# RAM_MAR_Circuit_Electronic_Scheme_2021-1.net
KiCad netlist of a schematic drawn in Altium Designer
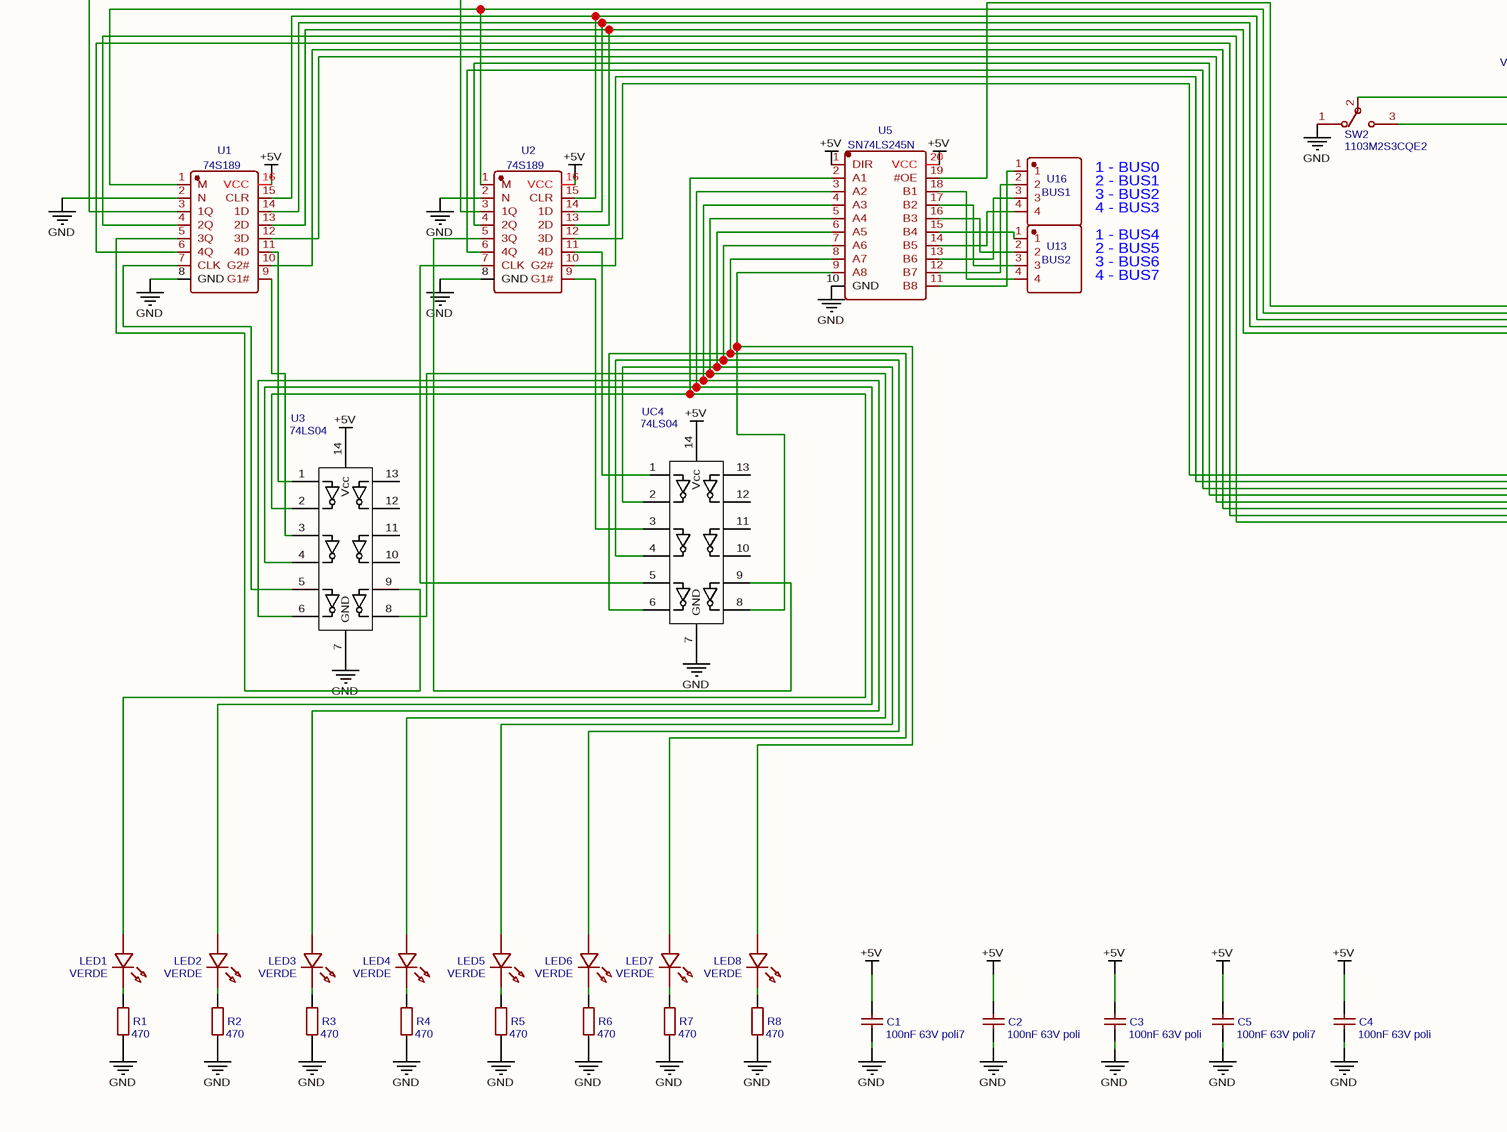
[diagram p0: RAM & MAR Circuit Electronic Scheme_2021-12-04.schdoc, left]
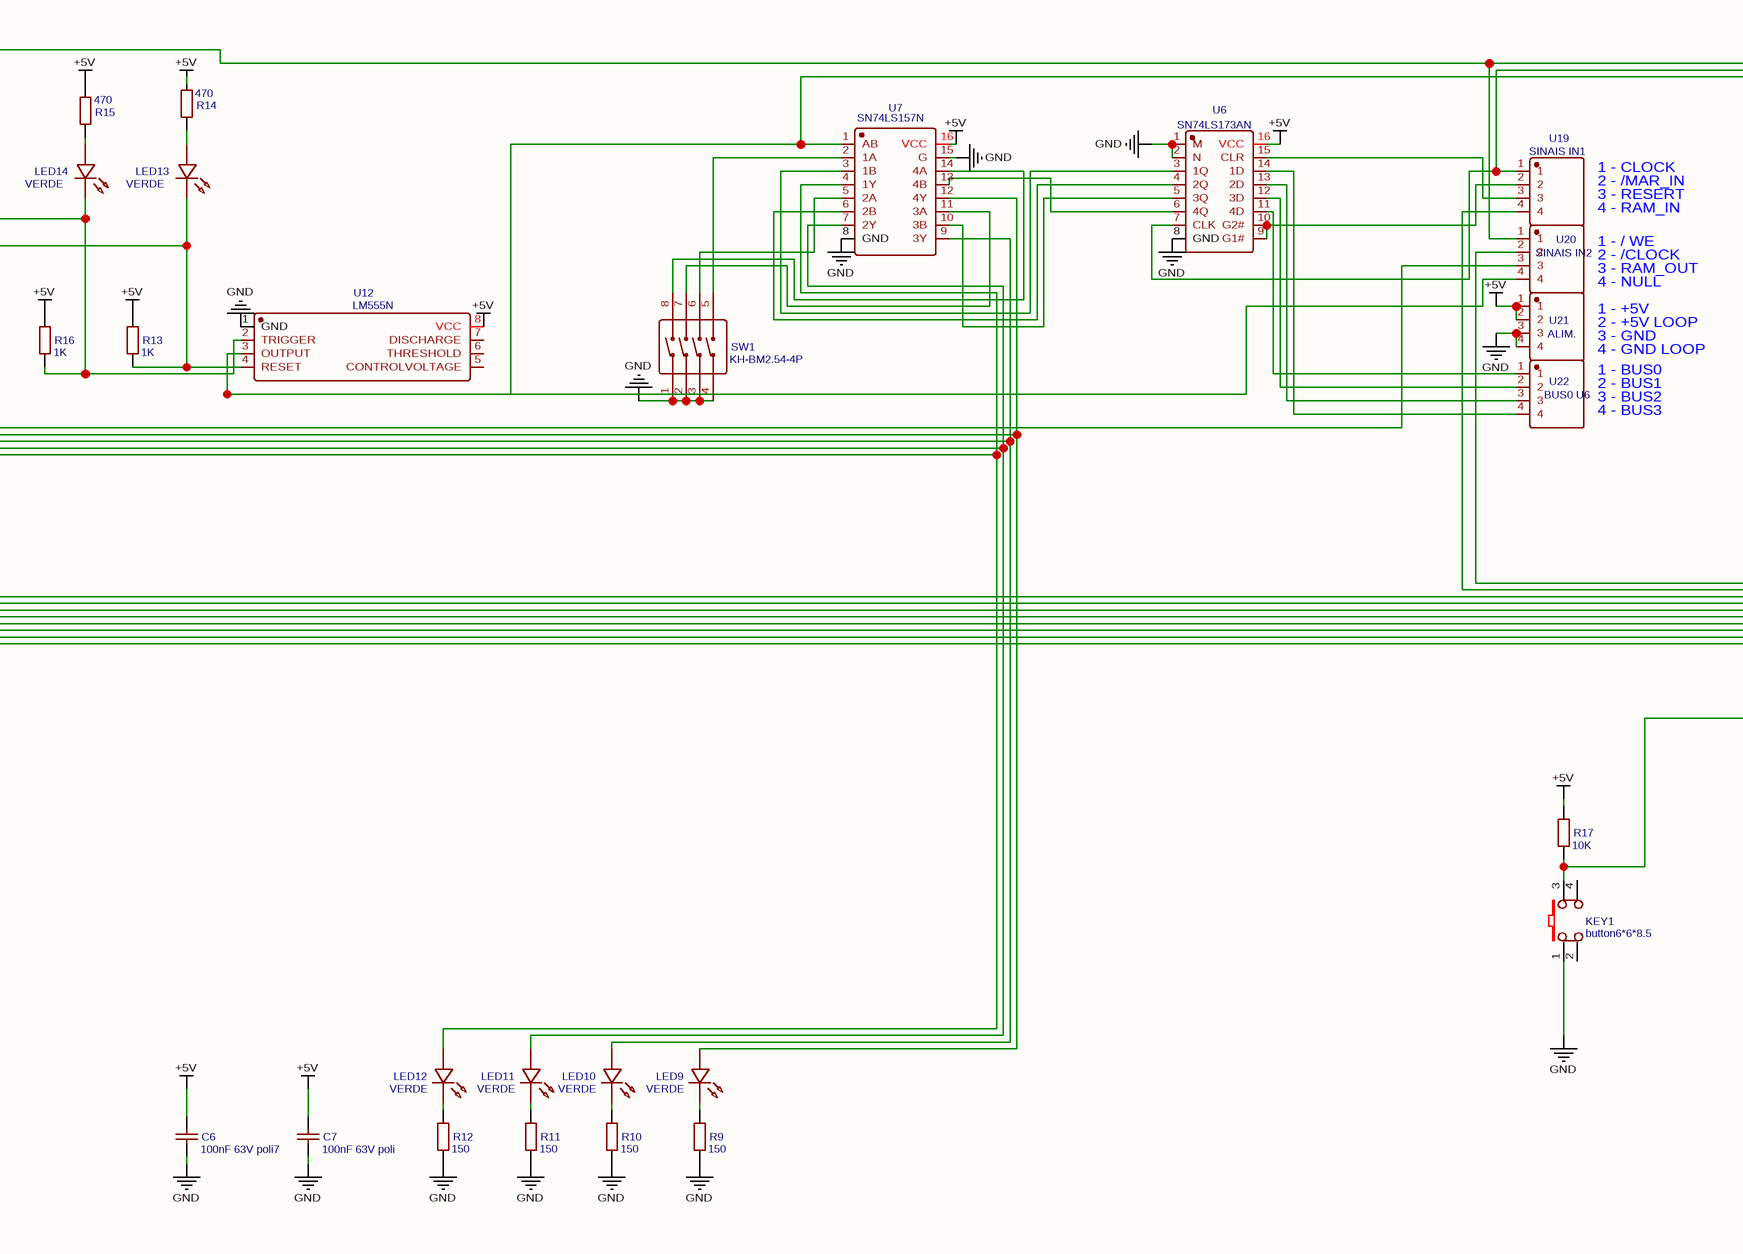
[diagram p1: RAM & MAR Circuit Electronic Scheme_2021-12-04.schdoc, middle]
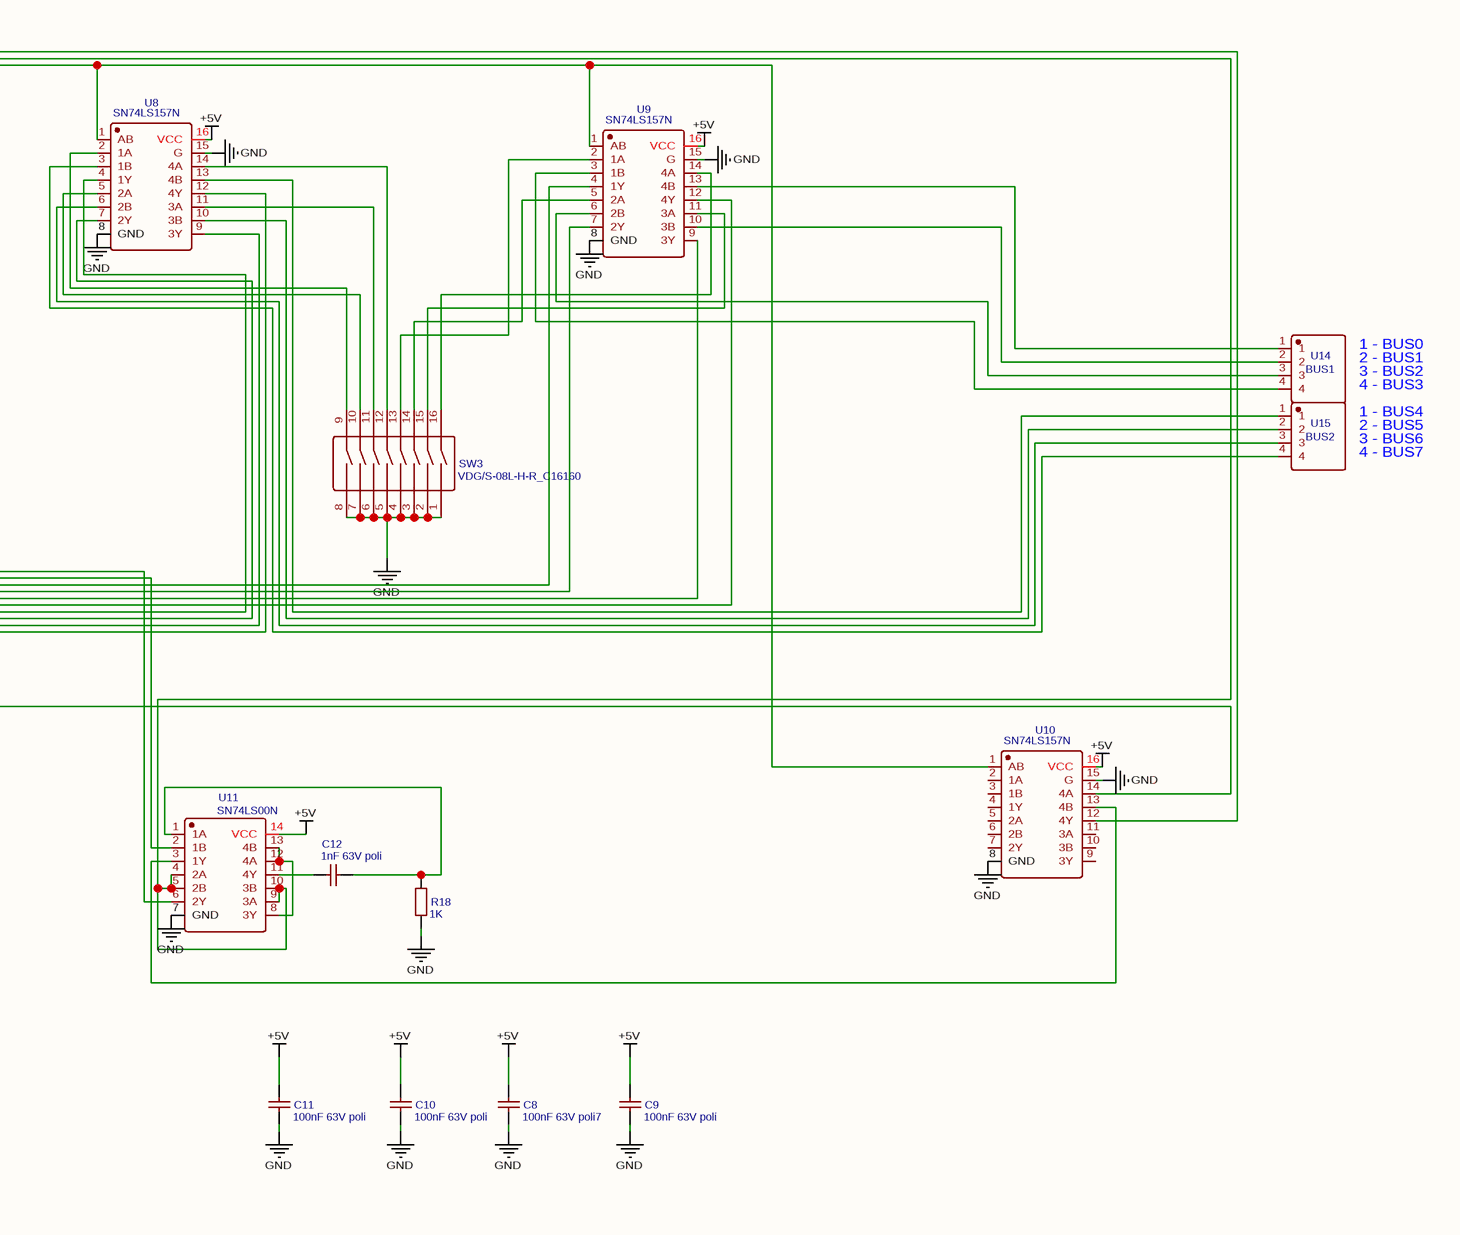
[diagram p2: RAM & MAR Circuit Electronic Scheme_2021-12-04.schdoc, right]

(export (version "E")
  (design (tool "Eeschema 10.0.6"))
  (components
    (comp (ref "C1")
      (value "100nF 63V poli7")
      (fields
        (field (name "BOM_SUPPLIER PART") "C444741")
        (field (name "BOM_MANUFACTURER PART") "SR305C105KAR")
      )
      (libsource (lib "altium-import") (part "root_3_100nF 63V poli7_"))
    )
    (comp (ref "C2")
      (value "100nF 63V poli")
      (fields
        (field (name "BOM_SUPPLIER PART") "C444741")
        (field (name "BOM_MANUFACTURER PART") "SR305C105KAR")
      )
      (libsource (lib "altium-import") (part "root_3_100nF 63V poli_"))
    )
    (comp (ref "C3")
      (value "100nF 63V poli")
      (fields
        (field (name "BOM_SUPPLIER PART") "C444741")
        (field (name "BOM_MANUFACTURER PART") "SR305C105KAR")
      )
      (libsource (lib "altium-import") (part "root_3_100nF 63V poli_"))
    )
    (comp (ref "C4")
      (value "100nF 63V poli")
      (fields
        (field (name "BOM_SUPPLIER PART") "C444741")
        (field (name "BOM_MANUFACTURER PART") "SR305C105KAR")
      )
      (libsource (lib "altium-import") (part "root_3_100nF 63V poli_"))
    )
    (comp (ref "C5")
      (value "100nF 63V poli7")
      (fields
        (field (name "BOM_SUPPLIER PART") "C444741")
        (field (name "BOM_MANUFACTURER PART") "SR305C105KAR")
      )
      (libsource (lib "altium-import") (part "root_3_100nF 63V poli7_"))
    )
    (comp (ref "C6")
      (value "100nF 63V poli7")
      (fields
        (field (name "BOM_SUPPLIER PART") "C444741")
        (field (name "BOM_MANUFACTURER PART") "SR305C105KAR")
      )
      (libsource (lib "altium-import") (part "root_3_100nF 63V poli7_"))
    )
    (comp (ref "C7")
      (value "100nF 63V poli")
      (fields
        (field (name "BOM_SUPPLIER PART") "C444741")
        (field (name "BOM_MANUFACTURER PART") "SR305C105KAR")
      )
      (libsource (lib "altium-import") (part "root_3_100nF 63V poli_"))
    )
    (comp (ref "C8")
      (value "100nF 63V poli7")
      (fields
        (field (name "BOM_SUPPLIER PART") "C444741")
        (field (name "BOM_MANUFACTURER PART") "SR305C105KAR")
      )
      (libsource (lib "altium-import") (part "root_3_100nF 63V poli7_"))
    )
    (comp (ref "C9")
      (value "100nF 63V poli")
      (fields
        (field (name "BOM_SUPPLIER PART") "C444741")
        (field (name "BOM_MANUFACTURER PART") "SR305C105KAR")
      )
      (libsource (lib "altium-import") (part "root_3_100nF 63V poli_"))
    )
    (comp (ref "C10")
      (value "100nF 63V poli")
      (fields
        (field (name "BOM_SUPPLIER PART") "C444741")
        (field (name "BOM_MANUFACTURER PART") "SR305C105KAR")
      )
      (libsource (lib "altium-import") (part "root_3_100nF 63V poli_"))
    )
    (comp (ref "C11")
      (value "100nF 63V poli")
      (fields
        (field (name "BOM_SUPPLIER PART") "C444741")
        (field (name "BOM_MANUFACTURER PART") "SR305C105KAR")
      )
      (libsource (lib "altium-import") (part "root_3_100nF 63V poli_"))
    )
    (comp (ref "C12")
      (value "1nF 63V poli")
      (fields
        (field (name "BOM_SUPPLIER PART") "C444741")
        (field (name "BOM_MANUFACTURER PART") "SR305C105KAR")
      )
      (libsource (lib "altium-import") (part "root_0_1nF 63V poli_"))
    )
    (comp (ref "KEY1")
      (value "button6*6*8.5")
      (fields (field (name "BOM_SUPPLIER PART") "C59980"))
      (libsource (lib "altium-import") (part "root_1_button6*6*8.5_"))
    )
    (comp (ref "LED1")
      (value "VERDE")
      (fields (field (name "BOM_SUPPLIER PART") "C605465") (field (name "BOM_MANUFACTURER PART") "264-7GD"))
      (libsource (lib "altium-import") (part "root_1_VERDE_"))
    )
    (comp (ref "LED2")
      (value "VERDE")
      (fields (field (name "BOM_SUPPLIER PART") "C605465") (field (name "BOM_MANUFACTURER PART") "264-7GD"))
      (libsource (lib "altium-import") (part "root_1_VERDE_"))
    )
    (comp (ref "LED3")
      (value "VERDE")
      (fields (field (name "BOM_SUPPLIER PART") "C605465") (field (name "BOM_MANUFACTURER PART") "264-7GD"))
      (libsource (lib "altium-import") (part "root_1_VERDE_"))
    )
    (comp (ref "LED4")
      (value "VERDE")
      (fields (field (name "BOM_SUPPLIER PART") "C605465") (field (name "BOM_MANUFACTURER PART") "264-7GD"))
      (libsource (lib "altium-import") (part "root_1_VERDE_"))
    )
    (comp (ref "LED5")
      (value "VERDE")
      (fields (field (name "BOM_SUPPLIER PART") "C605465") (field (name "BOM_MANUFACTURER PART") "264-7GD"))
      (libsource (lib "altium-import") (part "root_1_VERDE_"))
    )
    (comp (ref "LED6")
      (value "VERDE")
      (fields (field (name "BOM_SUPPLIER PART") "C605465") (field (name "BOM_MANUFACTURER PART") "264-7GD"))
      (libsource (lib "altium-import") (part "root_1_VERDE_"))
    )
    (comp (ref "LED7")
      (value "VERDE")
      (fields (field (name "BOM_SUPPLIER PART") "C605465") (field (name "BOM_MANUFACTURER PART") "264-7GD"))
      (libsource (lib "altium-import") (part "root_1_VERDE_"))
    )
    (comp (ref "LED8")
      (value "VERDE")
      (fields (field (name "BOM_SUPPLIER PART") "C605465") (field (name "BOM_MANUFACTURER PART") "264-7GD"))
      (libsource (lib "altium-import") (part "root_1_VERDE_"))
    )
    (comp (ref "LED9")
      (value "VERDE")
      (fields (field (name "BOM_SUPPLIER PART") "C605465") (field (name "BOM_MANUFACTURER PART") "264-7GD"))
      (libsource (lib "altium-import") (part "root_1_VERDE_"))
    )
    (comp (ref "LED10")
      (value "VERDE")
      (fields (field (name "BOM_SUPPLIER PART") "C605465") (field (name "BOM_MANUFACTURER PART") "264-7GD"))
      (libsource (lib "altium-import") (part "root_1_VERDE_"))
    )
    (comp (ref "LED11")
      (value "VERDE")
      (fields (field (name "BOM_SUPPLIER PART") "C605465") (field (name "BOM_MANUFACTURER PART") "264-7GD"))
      (libsource (lib "altium-import") (part "root_1_VERDE_"))
    )
    (comp (ref "LED12")
      (value "VERDE")
      (fields (field (name "BOM_SUPPLIER PART") "C605465") (field (name "BOM_MANUFACTURER PART") "264-7GD"))
      (libsource (lib "altium-import") (part "root_1_VERDE_"))
    )
    (comp (ref "LED13")
      (value "VERDE")
      (fields (field (name "BOM_SUPPLIER PART") "C605465") (field (name "BOM_MANUFACTURER PART") "264-7GD"))
      (libsource (lib "altium-import") (part "root_3_VERDE_"))
    )
    (comp (ref "LED14")
      (value "VERDE")
      (fields (field (name "BOM_SUPPLIER PART") "C605465") (field (name "BOM_MANUFACTURER PART") "264-7GD"))
      (libsource (lib "altium-import") (part "root_3_VERDE_"))
    )
    (comp (ref "R1")
      (value "470")
      (fields
        (field (name "BOM_MANUFACTURER PART") "CFR02SJ0823A10")
        (field (name "BOM_SUPPLIER PART") "C69876")
      )
      (libsource (lib "") (part "root_3_470__1"))
    )
    (comp (ref "R2")
      (value "470")
      (fields
        (field (name "BOM_MANUFACTURER PART") "CFR02SJ0823A10")
        (field (name "BOM_SUPPLIER PART") "C69876")
      )
      (libsource (lib "") (part "root_3_470__1"))
    )
    (comp (ref "R3")
      (value "470")
      (fields
        (field (name "BOM_MANUFACTURER PART") "CFR02SJ0823A10")
        (field (name "BOM_SUPPLIER PART") "C69876")
      )
      (libsource (lib "") (part "root_3_470__1"))
    )
    (comp (ref "R4")
      (value "470")
      (fields
        (field (name "BOM_MANUFACTURER PART") "CFR02SJ0823A10")
        (field (name "BOM_SUPPLIER PART") "C69876")
      )
      (libsource (lib "") (part "root_3_470__1"))
    )
    (comp (ref "R5")
      (value "470")
      (fields
        (field (name "BOM_MANUFACTURER PART") "CFR02SJ0823A10")
        (field (name "BOM_SUPPLIER PART") "C69876")
      )
      (libsource (lib "") (part "root_3_470__1"))
    )
    (comp (ref "R6")
      (value "470")
      (fields
        (field (name "BOM_MANUFACTURER PART") "CFR02SJ0823A10")
        (field (name "BOM_SUPPLIER PART") "C69876")
      )
      (libsource (lib "") (part "root_3_470__1"))
    )
    (comp (ref "R7")
      (value "470")
      (fields
        (field (name "BOM_MANUFACTURER PART") "CFR02SJ0823A10")
        (field (name "BOM_SUPPLIER PART") "C69876")
      )
      (libsource (lib "") (part "root_3_470__1"))
    )
    (comp (ref "R8")
      (value "470")
      (fields
        (field (name "BOM_MANUFACTURER PART") "CFR02SJ0823A10")
        (field (name "BOM_SUPPLIER PART") "C69876")
      )
      (libsource (lib "") (part "root_3_470__1"))
    )
    (comp (ref "R9")
      (value "150")
      (fields
        (field (name "BOM_MANUFACTURER PART") "CFR02SJ0823A10")
        (field (name "BOM_SUPPLIER PART") "C69876")
      )
      (libsource (lib "altium-import") (part "root_3_150_"))
    )
    (comp (ref "R10")
      (value "150")
      (fields
        (field (name "BOM_MANUFACTURER PART") "CFR02SJ0823A10")
        (field (name "BOM_SUPPLIER PART") "C69876")
      )
      (libsource (lib "altium-import") (part "root_3_150_"))
    )
    (comp (ref "R11")
      (value "150")
      (fields
        (field (name "BOM_MANUFACTURER PART") "CFR02SJ0823A10")
        (field (name "BOM_SUPPLIER PART") "C69876")
      )
      (libsource (lib "altium-import") (part "root_3_150_"))
    )
    (comp (ref "R12")
      (value "150")
      (fields
        (field (name "BOM_MANUFACTURER PART") "CFR02SJ0823A10")
        (field (name "BOM_SUPPLIER PART") "C69876")
      )
      (libsource (lib "altium-import") (part "root_3_150_"))
    )
    (comp (ref "R13")
      (value "1K")
      (fields
        (field (name "BOM_MANUFACTURER PART") "CFR02SJ0823A10")
        (field (name "BOM_SUPPLIER PART") "C69876")
      )
      (libsource (lib "altium-import") (part "root_3_1K_"))
    )
    (comp (ref "R14")
      (value "470")
      (fields
        (field (name "BOM_MANUFACTURER PART") "CFR02SJ0823A10")
        (field (name "BOM_SUPPLIER PART") "C69876")
      )
      (libsource (lib "altium-import") (part "root_3_470_"))
    )
    (comp (ref "R15")
      (value "470")
      (fields
        (field (name "BOM_MANUFACTURER PART") "CFR02SJ0823A10")
        (field (name "BOM_SUPPLIER PART") "C69876")
      )
      (libsource (lib "altium-import") (part "root_3_470_"))
    )
    (comp (ref "R16")
      (value "1K")
      (fields
        (field (name "BOM_MANUFACTURER PART") "CFR02SJ0823A10")
        (field (name "BOM_SUPPLIER PART") "C69876")
      )
      (libsource (lib "altium-import") (part "root_3_1K_"))
    )
    (comp (ref "R17")
      (value "10K")
      (fields
        (field (name "BOM_MANUFACTURER PART") "CFR02SJ0823A10")
        (field (name "BOM_SUPPLIER PART") "C69876")
      )
      (libsource (lib "altium-import") (part "root_3_10K_"))
    )
    (comp (ref "R18")
      (value "1K")
      (fields
        (field (name "BOM_MANUFACTURER PART") "CFR02SJ0823A10")
        (field (name "BOM_SUPPLIER PART") "C69876")
      )
      (libsource (lib "altium-import") (part "root_3_1K_"))
    )
    (comp (ref "SW1")
      (value "KH-BM2.54-4P")
      (fields (field (name "BOM_SUPPLIER PART") "C962226"))
      (libsource (lib "altium-import") (part "root_1_KH-BM2.54-4P_"))
    )
    (comp (ref "SW2")
      (value "1103M2S3CQE2")
      (fields (field (name "BOM_SUPPLIER PART") "C221539"))
      (libsource (lib "altium-import") (part "root_0_1103M2S3CQE2_"))
    )
    (comp (ref "SW3")
      (value "VDG/S-08L-H-R_C16160")
      (fields
        (field (name "BOM_MANUFACTURER PART") "VDG/S-08L-H-R")
        (field (name "BOM_SUPPLIER PART") "C16160")
      )
      (libsource (lib "altium-import") (part "root_2_VDG/S-08L-H-R_C16160_"))
    )
    (comp (ref "U1")
      (value "74S189")
      (fields
        (field (name "BOM_SUPPLIER PART") "C1550125")
        (field (name "BOM_MANUFACTURER PART") "SN74LS173AN")
      )
      (libsource (lib "altium-import") (part "root_0_74S189_"))
    )
    (comp (ref "U2")
      (value "74S189")
      (fields
        (field (name "BOM_SUPPLIER PART") "C1550125")
        (field (name "BOM_MANUFACTURER PART") "SN74LS173AN")
      )
      (libsource (lib "altium-import") (part "root_0_74S189_"))
    )
    (comp (ref "U3") (value "74LS04") (libsource (lib "altium-import") (part "root_0_74LS04_")))
    (comp (ref "U5")
      (value "SN74LS245N")
      (fields (field (name "BOM_SUPPLIER PART") "C352966"))
      (libsource (lib "altium-import") (part "root_0_SN74LS245N_"))
    )
    (comp (ref "U6")
      (value "SN74LS173AN")
      (fields (field (name "BOM_SUPPLIER PART") "C1550125"))
      (libsource (lib "altium-import") (part "root_0_SN74LS173AN_"))
    )
    (comp (ref "U7")
      (value "SN74LS157N")
      (fields (field (name "BOM_SUPPLIER PART") "C139317"))
      (libsource (lib "altium-import") (part "root_0_SN74LS157N_"))
    )
    (comp (ref "U8")
      (value "SN74LS157N")
      (fields (field (name "BOM_SUPPLIER PART") "C139317"))
      (libsource (lib "altium-import") (part "root_0_SN74LS157N_"))
    )
    (comp (ref "U9")
      (value "SN74LS157N")
      (fields (field (name "BOM_SUPPLIER PART") "C139317"))
      (libsource (lib "altium-import") (part "root_0_SN74LS157N_"))
    )
    (comp (ref "U10")
      (value "SN74LS157N")
      (fields (field (name "BOM_SUPPLIER PART") "C139317"))
      (libsource (lib "altium-import") (part "root_0_SN74LS157N_"))
    )
    (comp (ref "U11")
      (value "SN74LS00N")
      (fields (field (name "BOM_SUPPLIER PART") "C181629"))
      (libsource (lib "altium-import") (part "root_0_SN74LS00N_"))
    )
    (comp (ref "U12")
      (value "LM555N")
      (fields (field (name "BOM_SUPPLIER PART") "C725327"))
      (libsource (lib "altium-import") (part "root_0_LM555N_"))
    )
    (comp (ref "U13")
      (value "BUS2")
      (fields (field (name "BOM_SUPPLIER PART") "C210162") (field (name "BOM_MANUFACTURER PART") "171825-4"))
      (libsource (lib "altium-import") (part "root_0_BUS2_"))
    )
    (comp (ref "U14")
      (value "BUS1")
      (fields (field (name "BOM_SUPPLIER PART") "C210162") (field (name "BOM_MANUFACTURER PART") "171825-4"))
      (libsource (lib "altium-import") (part "root_0_BUS1_"))
    )
    (comp (ref "U15")
      (value "BUS2")
      (fields (field (name "BOM_SUPPLIER PART") "C210162") (field (name "BOM_MANUFACTURER PART") "171825-4"))
      (libsource (lib "altium-import") (part "root_0_BUS2_"))
    )
    (comp (ref "U16")
      (value "BUS1")
      (fields (field (name "BOM_SUPPLIER PART") "C210162") (field (name "BOM_MANUFACTURER PART") "171825-4"))
      (libsource (lib "altium-import") (part "root_0_BUS1_"))
    )
    (comp (ref "U19")
      (value "SINAIS IN1")
      (fields (field (name "BOM_SUPPLIER PART") "C210162") (field (name "BOM_MANUFACTURER PART") "171825-4"))
      (libsource (lib "altium-import") (part "root_0_SINAIS IN1_"))
    )
    (comp (ref "U20")
      (value "SINAIS IN2")
      (fields (field (name "BOM_SUPPLIER PART") "C210162") (field (name "BOM_MANUFACTURER PART") "171825-4"))
      (libsource (lib "altium-import") (part "root_0_SINAIS IN2_"))
    )
    (comp (ref "U21")
      (value "ALIM.")
      (fields (field (name "BOM_SUPPLIER PART") "C210162") (field (name "BOM_MANUFACTURER PART") "171825-4"))
      (libsource (lib "altium-import") (part "root_0_ALIM._"))
    )
    (comp (ref "U22")
      (value "BUS0 U6")
      (fields (field (name "BOM_SUPPLIER PART") "C210162") (field (name "BOM_MANUFACTURER PART") "171825-4"))
      (libsource (lib "altium-import") (part "root_0_BUS0 U6_"))
    )
    (comp (ref "UC4") (value "74LS04") (libsource (lib "altium-import") (part "root_0_74LS04_")))
  )
  (nets
    (net (code "1") (name "+5V") (class "Default")
      (node (ref "C1") (pin "1") (pinfunction "1_1") (pintype "passive"))
      (node (ref "C10") (pin "1") (pinfunction "1_1") (pintype "passive"))
      (node (ref "C11") (pin "1") (pinfunction "1_1") (pintype "passive"))
      (node (ref "C2") (pin "1") (pinfunction "1_1") (pintype "passive"))
      (node (ref "C3") (pin "1") (pinfunction "1_1") (pintype "passive"))
      (node (ref "C4") (pin "1") (pinfunction "1_1") (pintype "passive"))
      (node (ref "C5") (pin "1") (pinfunction "1_1") (pintype "passive"))
      (node (ref "C6") (pin "1") (pinfunction "1_1") (pintype "passive"))
      (node (ref "C7") (pin "1") (pinfunction "1_1") (pintype "passive"))
      (node (ref "C8") (pin "1") (pinfunction "1_1") (pintype "passive"))
      (node (ref "C9") (pin "1") (pinfunction "1_1") (pintype "passive"))
      (node (ref "R13") (pin "1") (pinfunction "1_1") (pintype "passive"))
      (node (ref "R14") (pin "2") (pinfunction "2_2") (pintype "passive"))
      (node (ref "R15") (pin "2") (pinfunction "2_2") (pintype "passive"))
      (node (ref "R16") (pin "1") (pinfunction "1_1") (pintype "passive"))
      (node (ref "R17") (pin "1") (pinfunction "1_1") (pintype "passive"))
      (node (ref "U1") (pin "16") (pinfunction "VCC_16") (pintype "passive"))
      (node (ref "U10") (pin "16") (pinfunction "VCC_16") (pintype "passive"))
      (node (ref "U11") (pin "14") (pinfunction "VCC_14") (pintype "passive"))
      (node (ref "U12") (pin "8") (pinfunction "VCC_8") (pintype "passive"))
      (node (ref "U2") (pin "16") (pinfunction "VCC_16") (pintype "passive"))
      (node (ref "U21") (pin "1") (pinfunction "1_1") (pintype "passive"))
      (node (ref "U21") (pin "2") (pinfunction "2_2") (pintype "passive"))
      (node (ref "U3") (pin "14") (pinfunction "Vcc_14") (pintype "passive"))
      (node (ref "U5") (pin "1") (pinfunction "DIR_1") (pintype "passive"))
      (node (ref "U5") (pin "20") (pinfunction "VCC_20") (pintype "passive"))
      (node (ref "U6") (pin "16") (pinfunction "VCC_16") (pintype "passive"))
      (node (ref "U7") (pin "16") (pinfunction "VCC_16") (pintype "passive"))
      (node (ref "U8") (pin "16") (pinfunction "VCC_16") (pintype "passive"))
      (node (ref "U9") (pin "16") (pinfunction "VCC_16") (pintype "passive"))
      (node (ref "UC4") (pin "14") (pinfunction "Vcc_14") (pintype "passive"))
    )
    (net (code "2") (name "GND") (class "Default")
      (node (ref "C1") (pin "2") (pinfunction "2_2") (pintype "passive"))
      (node (ref "C10") (pin "2") (pinfunction "2_2") (pintype "passive"))
      (node (ref "C11") (pin "2") (pinfunction "2_2") (pintype "passive"))
      (node (ref "C2") (pin "2") (pinfunction "2_2") (pintype "passive"))
      (node (ref "C3") (pin "2") (pinfunction "2_2") (pintype "passive"))
      (node (ref "C4") (pin "2") (pinfunction "2_2") (pintype "passive"))
      (node (ref "C5") (pin "2") (pinfunction "2_2") (pintype "passive"))
      (node (ref "C6") (pin "2") (pinfunction "2_2") (pintype "passive"))
      (node (ref "C7") (pin "2") (pinfunction "2_2") (pintype "passive"))
      (node (ref "C8") (pin "2") (pinfunction "2_2") (pintype "passive"))
      (node (ref "C9") (pin "2") (pinfunction "2_2") (pintype "passive"))
      (node (ref "KEY1") (pin "1") (pinfunction "1_1") (pintype "passive"))
      (node (ref "R1") (pin "2") (pinfunction "2_2") (pintype "passive"))
      (node (ref "R10") (pin "2") (pinfunction "2_2") (pintype "passive"))
      (node (ref "R11") (pin "2") (pinfunction "2_2") (pintype "passive"))
      (node (ref "R12") (pin "2") (pinfunction "2_2") (pintype "passive"))
      (node (ref "R18") (pin "2") (pinfunction "2_2") (pintype "passive"))
      (node (ref "R2") (pin "2") (pinfunction "2_2") (pintype "passive"))
      (node (ref "R3") (pin "2") (pinfunction "2_2") (pintype "passive"))
      (node (ref "R4") (pin "2") (pinfunction "2_2") (pintype "passive"))
      (node (ref "R5") (pin "2") (pinfunction "2_2") (pintype "passive"))
      (node (ref "R6") (pin "2") (pinfunction "2_2") (pintype "passive"))
      (node (ref "R7") (pin "2") (pinfunction "2_2") (pintype "passive"))
      (node (ref "R8") (pin "2") (pinfunction "2_2") (pintype "passive"))
      (node (ref "R9") (pin "2") (pinfunction "2_2") (pintype "passive"))
      (node (ref "SW1") (pin "1") (pinfunction "1_1") (pintype "passive"))
      (node (ref "SW1") (pin "2") (pinfunction "2_2") (pintype "passive"))
      (node (ref "SW1") (pin "3") (pinfunction "3_3") (pintype "passive"))
      (node (ref "SW1") (pin "4") (pinfunction "4_4") (pintype "passive"))
      (node (ref "SW2") (pin "1") (pinfunction "1_1") (pintype "passive"))
      (node (ref "SW3") (pin "1") (pinfunction "1_1") (pintype "passive"))
      (node (ref "SW3") (pin "2") (pinfunction "2_2") (pintype "passive"))
      (node (ref "SW3") (pin "3") (pinfunction "3_3") (pintype "passive"))
      (node (ref "SW3") (pin "4") (pinfunction "4_4") (pintype "passive"))
      (node (ref "SW3") (pin "5") (pinfunction "5_5") (pintype "passive"))
      (node (ref "SW3") (pin "6") (pinfunction "6_6") (pintype "passive"))
      (node (ref "SW3") (pin "7") (pinfunction "7_7") (pintype "passive"))
      (node (ref "SW3") (pin "8") (pinfunction "8_8") (pintype "passive"))
      (node (ref "U1") (pin "2") (pinfunction "N_2") (pintype "passive"))
      (node (ref "U1") (pin "8") (pinfunction "GND_8") (pintype "passive"))
      (node (ref "U10") (pin "15") (pinfunction "G_15") (pintype "passive"))
      (node (ref "U10") (pin "8") (pinfunction "GND_8") (pintype "passive"))
      (node (ref "U11") (pin "7") (pinfunction "GND_7") (pintype "passive"))
      (node (ref "U12") (pin "1") (pinfunction "GND_1") (pintype "passive"))
      (node (ref "U2") (pin "2") (pinfunction "N_2") (pintype "passive"))
      (node (ref "U2") (pin "8") (pinfunction "GND_8") (pintype "passive"))
      (node (ref "U21") (pin "3") (pinfunction "3_3") (pintype "passive"))
      (node (ref "U21") (pin "4") (pinfunction "4_4") (pintype "passive"))
      (node (ref "U3") (pin "7") (pinfunction "GND_7") (pintype "passive"))
      (node (ref "U5") (pin "10") (pinfunction "GND_10") (pintype "passive"))
      (node (ref "U6") (pin "1") (pinfunction "M_1") (pintype "passive"))
      (node (ref "U6") (pin "2") (pinfunction "N_2") (pintype "passive"))
      (node (ref "U6") (pin "8") (pinfunction "GND_8") (pintype "passive"))
      (node (ref "U7") (pin "15") (pinfunction "G_15") (pintype "passive"))
      (node (ref "U7") (pin "8") (pinfunction "GND_8") (pintype "passive"))
      (node (ref "U8") (pin "15") (pinfunction "G_15") (pintype "passive"))
      (node (ref "U8") (pin "8") (pinfunction "GND_8") (pintype "passive"))
      (node (ref "U9") (pin "15") (pinfunction "G_15") (pintype "passive"))
      (node (ref "U9") (pin "8") (pinfunction "GND_8") (pintype "passive"))
      (node (ref "UC4") (pin "7") (pinfunction "GND_7") (pintype "passive"))
    )
    (net (code "3") (name "Net-(LED1-+)") (class "Default")
      (node (ref "LED1") (pin "2") (pinfunction "+_2") (pintype "passive"))
      (node (ref "U3") (pin "2") (pintype "passive"))
      (node (ref "U5") (pin "2") (pinfunction "A1_2") (pintype "passive"))
    )
    (net (code "4") (name "Net-(LED1--)") (class "Default")
      (node (ref "LED1") (pin "1") (pinfunction "-_1") (pintype "passive"))
      (node (ref "R1") (pin "1") (pinfunction "1_1") (pintype "passive"))
    )
    (net (code "5") (name "Net-(LED2-+)") (class "Default")
      (node (ref "LED2") (pin "2") (pinfunction "+_2") (pintype "passive"))
      (node (ref "U3") (pin "4") (pintype "passive"))
      (node (ref "U5") (pin "3") (pinfunction "A2_3") (pintype "passive"))
    )
    (net (code "6") (name "Net-(LED2--)") (class "Default")
      (node (ref "LED2") (pin "1") (pinfunction "-_1") (pintype "passive"))
      (node (ref "R2") (pin "1") (pinfunction "1_1") (pintype "passive"))
    )
    (net (code "7") (name "Net-(LED3-+)") (class "Default")
      (node (ref "LED3") (pin "2") (pinfunction "+_2") (pintype "passive"))
      (node (ref "U3") (pin "6") (pintype "passive"))
      (node (ref "U5") (pin "4") (pinfunction "A3_4") (pintype "passive"))
    )
    (net (code "8") (name "Net-(LED3--)") (class "Default")
      (node (ref "LED3") (pin "1") (pinfunction "-_1") (pintype "passive"))
      (node (ref "R3") (pin "1") (pinfunction "1_1") (pintype "passive"))
    )
    (net (code "9") (name "Net-(LED4-+)") (class "Default")
      (node (ref "LED4") (pin "2") (pinfunction "+_2") (pintype "passive"))
      (node (ref "U3") (pin "8") (pintype "passive"))
      (node (ref "U5") (pin "5") (pinfunction "A4_5") (pintype "passive"))
    )
    (net (code "10") (name "Net-(LED4--)") (class "Default")
      (node (ref "LED4") (pin "1") (pinfunction "-_1") (pintype "passive"))
      (node (ref "R4") (pin "1") (pinfunction "1_1") (pintype "passive"))
    )
    (net (code "11") (name "Net-(LED5-+)") (class "Default")
      (node (ref "LED5") (pin "2") (pinfunction "+_2") (pintype "passive"))
      (node (ref "U5") (pin "6") (pinfunction "A5_6") (pintype "passive"))
      (node (ref "UC4") (pin "2") (pintype "passive"))
    )
    (net (code "12") (name "Net-(LED5--)") (class "Default")
      (node (ref "LED5") (pin "1") (pinfunction "-_1") (pintype "passive"))
      (node (ref "R5") (pin "1") (pinfunction "1_1") (pintype "passive"))
    )
    (net (code "13") (name "Net-(LED6-+)") (class "Default")
      (node (ref "LED6") (pin "2") (pinfunction "+_2") (pintype "passive"))
      (node (ref "U5") (pin "7") (pinfunction "A6_7") (pintype "passive"))
      (node (ref "UC4") (pin "4") (pintype "passive"))
    )
    (net (code "14") (name "Net-(LED6--)") (class "Default")
      (node (ref "LED6") (pin "1") (pinfunction "-_1") (pintype "passive"))
      (node (ref "R6") (pin "1") (pinfunction "1_1") (pintype "passive"))
    )
    (net (code "15") (name "Net-(LED7-+)") (class "Default")
      (node (ref "LED7") (pin "2") (pinfunction "+_2") (pintype "passive"))
      (node (ref "U5") (pin "8") (pinfunction "A7_8") (pintype "passive"))
      (node (ref "UC4") (pin "6") (pintype "passive"))
    )
    (net (code "16") (name "Net-(LED7--)") (class "Default")
      (node (ref "LED7") (pin "1") (pinfunction "-_1") (pintype "passive"))
      (node (ref "R7") (pin "1") (pinfunction "1_1") (pintype "passive"))
    )
    (net (code "17") (name "Net-(LED8-+)") (class "Default")
      (node (ref "LED8") (pin "2") (pinfunction "+_2") (pintype "passive"))
      (node (ref "U5") (pin "9") (pinfunction "A8_9") (pintype "passive"))
      (node (ref "UC4") (pin "8") (pintype "passive"))
    )
    (net (code "18") (name "Net-(LED8--)") (class "Default")
      (node (ref "LED8") (pin "1") (pinfunction "-_1") (pintype "passive"))
      (node (ref "R8") (pin "1") (pinfunction "1_1") (pintype "passive"))
    )
    (net (code "19") (name "Net-(LED9-+)") (class "Default")
      (node (ref "LED9") (pin "2") (pinfunction "+_2") (pintype "passive"))
      (node (ref "U1") (pin "1") (pinfunction "M_1") (pintype "passive"))
      (node (ref "U2") (pin "1") (pinfunction "M_1") (pintype "passive"))
      (node (ref "U7") (pin "12") (pinfunction "4Y_12") (pintype "passive"))
    )
    (net (code "20") (name "Net-(LED9--)") (class "Default")
      (node (ref "LED9") (pin "1") (pinfunction "-_1") (pintype "passive"))
      (node (ref "R9") (pin "1") (pinfunction "1_1") (pintype "passive"))
    )
    (net (code "21") (name "Net-(LED10-+)") (class "Default")
      (node (ref "LED10") (pin "2") (pinfunction "+_2") (pintype "passive"))
      (node (ref "U1") (pin "15") (pinfunction "CLR_15") (pintype "passive"))
      (node (ref "U2") (pin "15") (pinfunction "CLR_15") (pintype "passive"))
      (node (ref "U7") (pin "9") (pinfunction "3Y_9") (pintype "passive"))
    )
    (net (code "22") (name "Net-(LED10--)") (class "Default")
      (node (ref "LED10") (pin "1") (pinfunction "-_1") (pintype "passive"))
      (node (ref "R10") (pin "1") (pinfunction "1_1") (pintype "passive"))
    )
    (net (code "23") (name "Net-(LED11-+)") (class "Default")
      (node (ref "LED11") (pin "2") (pinfunction "+_2") (pintype "passive"))
      (node (ref "U1") (pin "14") (pinfunction "1D_14") (pintype "passive"))
      (node (ref "U2") (pin "14") (pinfunction "1D_14") (pintype "passive"))
      (node (ref "U7") (pin "7") (pinfunction "2Y_7") (pintype "passive"))
    )
    (net (code "24") (name "Net-(LED11--)") (class "Default")
      (node (ref "LED11") (pin "1") (pinfunction "-_1") (pintype "passive"))
      (node (ref "R11") (pin "1") (pinfunction "1_1") (pintype "passive"))
    )
    (net (code "25") (name "Net-(LED12-+)") (class "Default")
      (node (ref "LED12") (pin "2") (pinfunction "+_2") (pintype "passive"))
      (node (ref "U1") (pin "13") (pinfunction "2D_13") (pintype "passive"))
      (node (ref "U2") (pin "13") (pinfunction "2D_13") (pintype "passive"))
      (node (ref "U7") (pin "4") (pinfunction "1Y_4") (pintype "passive"))
    )
    (net (code "26") (name "Net-(LED12--)") (class "Default")
      (node (ref "LED12") (pin "1") (pinfunction "-_1") (pintype "passive"))
      (node (ref "R12") (pin "1") (pinfunction "1_1") (pintype "passive"))
    )
    (net (code "27") (name "Net-(LED13-+)") (class "Default")
      (node (ref "LED13") (pin "2") (pinfunction "+_2") (pintype "passive"))
      (node (ref "R14") (pin "1") (pinfunction "1_1") (pintype "passive"))
    )
    (net (code "28") (name "Net-(LED13--)") (class "Default")
      (node (ref "LED13") (pin "1") (pinfunction "-_1") (pintype "passive"))
      (node (ref "R13") (pin "2") (pinfunction "2_2") (pintype "passive"))
      (node (ref "SW2") (pin "3") (pinfunction "3_3") (pintype "passive"))
      (node (ref "U12") (pin "4") (pinfunction "RESET_4") (pintype "passive"))
    )
    (net (code "29") (name "Net-(LED14-+)") (class "Default")
      (node (ref "LED14") (pin "2") (pinfunction "+_2") (pintype "passive"))
      (node (ref "R15") (pin "1") (pinfunction "1_1") (pintype "passive"))
    )
    (net (code "30") (name "Net-(LED14--)") (class "Default")
      (node (ref "LED14") (pin "1") (pinfunction "-_1") (pintype "passive"))
      (node (ref "R16") (pin "2") (pinfunction "2_2") (pintype "passive"))
      (node (ref "SW2") (pin "2") (pinfunction "2_2") (pintype "passive"))
      (node (ref "U12") (pin "2") (pinfunction "TRIGGER_2") (pintype "passive"))
    )
    (net (code "31") (name "Net-(U1-1Q)") (class "Default")
      (node (ref "U1") (pin "3") (pinfunction "1Q_3") (pintype "passive"))
      (node (ref "U10") (pin "12") (pinfunction "4Y_12") (pintype "passive"))
      (node (ref "U2") (pin "3") (pinfunction "1Q_3") (pintype "passive"))
      (node (ref "U20") (pin "1") (pinfunction "1_1") (pintype "passive"))
    )
    (net (code "32") (name "Net-(U1-2Q)") (class "Default")
      (node (ref "U1") (pin "4") (pinfunction "2Q_4") (pintype "passive"))
      (node (ref "U8") (pin "12") (pinfunction "4Y_12") (pintype "passive"))
    )
    (net (code "33") (name "Net-(U1-3D)") (class "Default")
      (node (ref "U1") (pin "12") (pinfunction "3D_12") (pintype "passive"))
      (node (ref "U8") (pin "4") (pinfunction "1Y_4") (pintype "passive"))
    )
    (net (code "34") (name "Net-(U1-3Q)") (class "Default")
      (node (ref "U1") (pin "5") (pinfunction "3Q_5") (pintype "passive"))
      (node (ref "U3") (pin "9") (pintype "passive"))
    )
    (net (code "35") (name "Net-(U1-4D)") (class "Default")
      (node (ref "U1") (pin "11") (pinfunction "4D_11") (pintype "passive"))
      (node (ref "U3") (pin "1") (pintype "passive"))
    )
    (net (code "36") (name "Net-(U1-4Q)") (class "Default")
      (node (ref "U1") (pin "6") (pinfunction "4Q_6") (pintype "passive"))
      (node (ref "U8") (pin "9") (pinfunction "3Y_9") (pintype "passive"))
    )
    (net (code "37") (name "Net-(U1-CLK)") (class "Default")
      (node (ref "U1") (pin "7") (pinfunction "CLK_7") (pintype "passive"))
      (node (ref "U3") (pin "5") (pintype "passive"))
    )
    (net (code "38") (name "Net-(U1-G1#)") (class "Default")
      (node (ref "U1") (pin "9") (pinfunction "G1#_9") (pintype "passive"))
      (node (ref "U3") (pin "3") (pintype "passive"))
    )
    (net (code "39") (name "Net-(U1-G2#)") (class "Default")
      (node (ref "U1") (pin "10") (pinfunction "G2#_10") (pintype "passive"))
      (node (ref "U8") (pin "7") (pinfunction "2Y_7") (pintype "passive"))
    )
    (net (code "40") (name "Net-(U2-2Q)") (class "Default")
      (node (ref "U2") (pin "4") (pinfunction "2Q_4") (pintype "passive"))
      (node (ref "U9") (pin "12") (pinfunction "4Y_12") (pintype "passive"))
    )
    (net (code "41") (name "Net-(U2-3D)") (class "Default")
      (node (ref "U2") (pin "12") (pinfunction "3D_12") (pintype "passive"))
      (node (ref "U9") (pin "4") (pinfunction "1Y_4") (pintype "passive"))
    )
    (net (code "42") (name "Net-(U2-3Q)") (class "Default")
      (node (ref "U2") (pin "5") (pinfunction "3Q_5") (pintype "passive"))
      (node (ref "UC4") (pin "9") (pintype "passive"))
    )
    (net (code "43") (name "Net-(U2-4D)") (class "Default")
      (node (ref "U2") (pin "11") (pinfunction "4D_11") (pintype "passive"))
      (node (ref "UC4") (pin "1") (pintype "passive"))
    )
    (net (code "44") (name "Net-(U2-4Q)") (class "Default")
      (node (ref "U2") (pin "6") (pinfunction "4Q_6") (pintype "passive"))
      (node (ref "U9") (pin "9") (pinfunction "3Y_9") (pintype "passive"))
    )
    (net (code "45") (name "Net-(U2-CLK)") (class "Default")
      (node (ref "U2") (pin "7") (pinfunction "CLK_7") (pintype "passive"))
      (node (ref "UC4") (pin "5") (pintype "passive"))
    )
    (net (code "46") (name "Net-(U2-G1#)") (class "Default")
      (node (ref "U2") (pin "9") (pinfunction "G1#_9") (pintype "passive"))
      (node (ref "UC4") (pin "3") (pintype "passive"))
    )
    (net (code "47") (name "Net-(U2-G2#)") (class "Default")
      (node (ref "U2") (pin "10") (pinfunction "G2#_10") (pintype "passive"))
      (node (ref "U9") (pin "7") (pinfunction "2Y_7") (pintype "passive"))
    )
    (net (code "48") (name "Net-(U5-#OE)") (class "Default")
      (node (ref "U20") (pin "3") (pinfunction "3_3") (pintype "passive"))
      (node (ref "U5") (pin "19") (pinfunction "#OE_19") (pintype "passive"))
    )
    (net (code "49") (name "Net-(U5-B1)") (class "Default")
      (node (ref "U13") (pin "4") (pinfunction "4_4") (pintype "passive"))
      (node (ref "U5") (pin "18") (pinfunction "B1_18") (pintype "passive"))
    )
    (net (code "50") (name "Net-(U5-B2)") (class "Default")
      (node (ref "U13") (pin "3") (pinfunction "3_3") (pintype "passive"))
      (node (ref "U5") (pin "17") (pinfunction "B2_17") (pintype "passive"))
    )
    (net (code "51") (name "Net-(U5-B3)") (class "Default")
      (node (ref "U13") (pin "2") (pinfunction "2_2") (pintype "passive"))
      (node (ref "U5") (pin "16") (pinfunction "B3_16") (pintype "passive"))
    )
    (net (code "52") (name "Net-(U5-B4)") (class "Default")
      (node (ref "U13") (pin "1") (pinfunction "1_1") (pintype "passive"))
      (node (ref "U5") (pin "15") (pinfunction "B4_15") (pintype "passive"))
    )
    (net (code "53") (name "Net-(U5-B5)") (class "Default")
      (node (ref "U16") (pin "4") (pinfunction "4_4") (pintype "passive"))
      (node (ref "U5") (pin "14") (pinfunction "B5_14") (pintype "passive"))
    )
    (net (code "54") (name "Net-(U5-B6)") (class "Default")
      (node (ref "U16") (pin "3") (pinfunction "3_3") (pintype "passive"))
      (node (ref "U5") (pin "13") (pinfunction "B6_13") (pintype "passive"))
    )
    (net (code "55") (name "Net-(U5-B7)") (class "Default")
      (node (ref "U16") (pin "2") (pinfunction "2_2") (pintype "passive"))
      (node (ref "U5") (pin "12") (pinfunction "B7_12") (pintype "passive"))
    )
    (net (code "56") (name "Net-(U5-B8)") (class "Default")
      (node (ref "U16") (pin "1") (pinfunction "1_1") (pintype "passive"))
      (node (ref "U5") (pin "11") (pinfunction "B8_11") (pintype "passive"))
    )
    (net (code "57") (name "Net-(U6-1D)") (class "Default")
      (node (ref "U22") (pin "4") (pinfunction "4_4") (pintype "passive"))
      (node (ref "U6") (pin "14") (pinfunction "1D_14") (pintype "passive"))
    )
    (net (code "58") (name "Net-(U6-1Q)") (class "Default")
      (node (ref "U6") (pin "3") (pinfunction "1Q_3") (pintype "passive"))
      (node (ref "U7") (pin "3") (pinfunction "1B_3") (pintype "passive"))
    )
    (net (code "59") (name "Net-(U6-2D)") (class "Default")
      (node (ref "U22") (pin "3") (pinfunction "3_3") (pintype "passive"))
      (node (ref "U6") (pin "13") (pinfunction "2D_13") (pintype "passive"))
    )
    (net (code "60") (name "Net-(U6-2Q)") (class "Default")
      (node (ref "U6") (pin "4") (pinfunction "2Q_4") (pintype "passive"))
      (node (ref "U7") (pin "6") (pinfunction "2B_6") (pintype "passive"))
    )
    (net (code "61") (name "Net-(U6-3D)") (class "Default")
      (node (ref "U22") (pin "2") (pinfunction "2_2") (pintype "passive"))
      (node (ref "U6") (pin "12") (pinfunction "3D_12") (pintype "passive"))
    )
    (net (code "62") (name "Net-(U6-3Q)") (class "Default")
      (node (ref "U6") (pin "5") (pinfunction "3Q_5") (pintype "passive"))
      (node (ref "U7") (pin "10") (pinfunction "3B_10") (pintype "passive"))
    )
    (net (code "63") (name "Net-(U6-4D)") (class "Default")
      (node (ref "U22") (pin "1") (pinfunction "1_1") (pintype "passive"))
      (node (ref "U6") (pin "11") (pinfunction "4D_11") (pintype "passive"))
    )
    (net (code "64") (name "Net-(U6-4Q)") (class "Default")
      (node (ref "U6") (pin "6") (pinfunction "4Q_6") (pintype "passive"))
      (node (ref "U7") (pin "13") (pinfunction "4B_13") (pintype "passive"))
    )
    (net (code "65") (name "Net-(U6-CLR)") (class "Default")
      (node (ref "U19") (pin "3") (pinfunction "3_3") (pintype "passive"))
      (node (ref "U6") (pin "15") (pinfunction "CLR_15") (pintype "passive"))
    )
    (net (code "66") (name "Net-(U6-G1#)") (class "Default")
      (node (ref "U19") (pin "2") (pinfunction "2_2") (pintype "passive"))
      (node (ref "U6") (pin "10") (pinfunction "G2#_10") (pintype "passive"))
      (node (ref "U6") (pin "9") (pinfunction "G1#_9") (pintype "passive"))
    )
    (net (code "67") (name "Net-(U7-1A)") (class "Default")
      (node (ref "SW1") (pin "5") (pinfunction "5_5") (pintype "passive"))
      (node (ref "U7") (pin "2") (pinfunction "1A_2") (pintype "passive"))
    )
    (net (code "68") (name "Net-(U7-2A)") (class "Default")
      (node (ref "SW1") (pin "6") (pinfunction "6_6") (pintype "passive"))
      (node (ref "U7") (pin "5") (pinfunction "2A_5") (pintype "passive"))
    )
    (net (code "69") (name "Net-(U7-3A)") (class "Default")
      (node (ref "SW1") (pin "7") (pinfunction "7_7") (pintype "passive"))
      (node (ref "U7") (pin "11") (pinfunction "3A_11") (pintype "passive"))
    )
    (net (code "70") (name "Net-(U7-4A)") (class "Default")
      (node (ref "SW1") (pin "8") (pinfunction "8_8") (pintype "passive"))
      (node (ref "U7") (pin "14") (pinfunction "4A_14") (pintype "passive"))
    )
    (net (code "71") (name "Net-(U8-1A)") (class "Default")
      (node (ref "SW3") (pin "9") (pinfunction "9_9") (pintype "passive"))
      (node (ref "U8") (pin "2") (pinfunction "1A_2") (pintype "passive"))
    )
    (net (code "72") (name "Net-(U8-1B)") (class "Default")
      (node (ref "U15") (pin "4") (pinfunction "4_4") (pintype "passive"))
      (node (ref "U8") (pin "3") (pinfunction "1B_3") (pintype "passive"))
    )
    (net (code "73") (name "Net-(U8-2A)") (class "Default")
      (node (ref "SW3") (pin "10") (pinfunction "10_10") (pintype "passive"))
      (node (ref "U8") (pin "5") (pinfunction "2A_5") (pintype "passive"))
    )
    (net (code "74") (name "Net-(U8-2B)") (class "Default")
      (node (ref "U15") (pin "3") (pinfunction "3_3") (pintype "passive"))
      (node (ref "U8") (pin "6") (pinfunction "2B_6") (pintype "passive"))
    )
    (net (code "75") (name "Net-(U8-3A)") (class "Default")
      (node (ref "SW3") (pin "11") (pinfunction "11_11") (pintype "passive"))
      (node (ref "U8") (pin "11") (pinfunction "3A_11") (pintype "passive"))
    )
    (net (code "76") (name "Net-(U8-3B)") (class "Default")
      (node (ref "U15") (pin "2") (pinfunction "2_2") (pintype "passive"))
      (node (ref "U8") (pin "10") (pinfunction "3B_10") (pintype "passive"))
    )
    (net (code "77") (name "Net-(U8-4A)") (class "Default")
      (node (ref "SW3") (pin "12") (pinfunction "12_12") (pintype "passive"))
      (node (ref "U8") (pin "14") (pinfunction "4A_14") (pintype "passive"))
    )
    (net (code "78") (name "Net-(U8-4B)") (class "Default")
      (node (ref "U15") (pin "1") (pinfunction "1_1") (pintype "passive"))
      (node (ref "U8") (pin "13") (pinfunction "4B_13") (pintype "passive"))
    )
    (net (code "79") (name "Net-(U9-1A)") (class "Default")
      (node (ref "SW3") (pin "13") (pinfunction "13_13") (pintype "passive"))
      (node (ref "U9") (pin "2") (pinfunction "1A_2") (pintype "passive"))
    )
    (net (code "80") (name "Net-(U9-1B)") (class "Default")
      (node (ref "U14") (pin "4") (pinfunction "4_4") (pintype "passive"))
      (node (ref "U9") (pin "3") (pinfunction "1B_3") (pintype "passive"))
    )
    (net (code "81") (name "Net-(U9-2A)") (class "Default")
      (node (ref "SW3") (pin "14") (pinfunction "14_14") (pintype "passive"))
      (node (ref "U9") (pin "5") (pinfunction "2A_5") (pintype "passive"))
    )
    (net (code "82") (name "Net-(U9-2B)") (class "Default")
      (node (ref "U14") (pin "3") (pinfunction "3_3") (pintype "passive"))
      (node (ref "U9") (pin "6") (pinfunction "2B_6") (pintype "passive"))
    )
    (net (code "83") (name "Net-(U9-3A)") (class "Default")
      (node (ref "SW3") (pin "15") (pinfunction "15_15") (pintype "passive"))
      (node (ref "U9") (pin "11") (pinfunction "3A_11") (pintype "passive"))
    )
    (net (code "84") (name "Net-(U9-3B)") (class "Default")
      (node (ref "U14") (pin "2") (pinfunction "2_2") (pintype "passive"))
      (node (ref "U9") (pin "10") (pinfunction "3B_10") (pintype "passive"))
    )
    (net (code "85") (name "Net-(U9-4A)") (class "Default")
      (node (ref "SW3") (pin "16") (pinfunction "16_16") (pintype "passive"))
      (node (ref "U9") (pin "14") (pinfunction "4A_14") (pintype "passive"))
    )
    (net (code "86") (name "Net-(U9-4B)") (class "Default")
      (node (ref "U14") (pin "1") (pinfunction "1_1") (pintype "passive"))
      (node (ref "U9") (pin "13") (pinfunction "4B_13") (pintype "passive"))
    )
    (net (code "87") (name "Net-(U10-4A)") (class "Default")
      (node (ref "KEY1") (pin "3") (pinfunction "3_3") (pintype "passive"))
      (node (ref "R17") (pin "2") (pinfunction "2_2") (pintype "passive"))
      (node (ref "U10") (pin "14") (pinfunction "4A_14") (pintype "passive"))
    )
    (net (code "88") (name "Net-(U10-4B)") (class "Default")
      (node (ref "U10") (pin "13") (pinfunction "4B_13") (pintype "passive"))
      (node (ref "U11") (pin "3") (pinfunction "1Y_3") (pintype "passive"))
    )
    (net (code "89") (name "Net-(U10-AB)") (class "Default")
      (node (ref "U10") (pin "1") (pinfunction "AB_1") (pintype "passive"))
      (node (ref "U12") (pin "3") (pinfunction "OUTPUT_3") (pintype "passive"))
      (node (ref "U20") (pin "4") (pinfunction "4_4") (pintype "passive"))
      (node (ref "U7") (pin "1") (pinfunction "AB_1") (pintype "passive"))
      (node (ref "U8") (pin "1") (pinfunction "AB_1") (pintype "passive"))
      (node (ref "U9") (pin "1") (pinfunction "AB_1") (pintype "passive"))
    )
    (net (code "90") (name "Net-(U11-1A)") (class "Default")
      (node (ref "C12") (pin "2") (pinfunction "2_2") (pintype "passive"))
      (node (ref "R18") (pin "1") (pinfunction "1_1") (pintype "passive"))
      (node (ref "U11") (pin "1") (pinfunction "1A_1") (pintype "passive"))
    )
    (net (code "91") (name "Net-(U11-1B)") (class "Default")
      (node (ref "U11") (pin "2") (pinfunction "1B_2") (pintype "passive"))
      (node (ref "U19") (pin "4") (pinfunction "4_4") (pintype "passive"))
    )
    (net (code "92") (name "Net-(U11-2A)") (class "Default")
      (node (ref "U11") (pin "10") (pinfunction "3B_10") (pintype "passive"))
      (node (ref "U11") (pin "4") (pinfunction "2A_4") (pintype "passive"))
      (node (ref "U11") (pin "5") (pinfunction "2B_5") (pintype "passive"))
      (node (ref "U11") (pin "9") (pinfunction "3A_9") (pintype "passive"))
      (node (ref "U19") (pin "1") (pinfunction "1_1") (pintype "passive"))
      (node (ref "U6") (pin "7") (pinfunction "CLK_7") (pintype "passive"))
    )
    (net (code "93") (name "Net-(U11-2Y)") (class "Default")
      (node (ref "U11") (pin "6") (pinfunction "2Y_6") (pintype "passive"))
      (node (ref "U20") (pin "2") (pinfunction "2_2") (pintype "passive"))
    )
    (net (code "94") (name "Net-(U11-3Y)") (class "Default")
      (node (ref "U11") (pin "12") (pinfunction "4A_12") (pintype "passive"))
      (node (ref "U11") (pin "13") (pinfunction "4B_13") (pintype "passive"))
      (node (ref "U11") (pin "8") (pinfunction "3Y_8") (pintype "passive"))
    )
    (net (code "95") (name "Net-(U11-4Y)") (class "Default")
      (node (ref "C12") (pin "1") (pinfunction "1_1") (pintype "passive"))
      (node (ref "U11") (pin "11") (pinfunction "4Y_11") (pintype "passive"))
    )
    (net (code "96") (name "unconnected-(KEY1-Pad2)") (class "Default")
      (node (ref "KEY1") (pin "2") (pinfunction "2_2") (pintype "passive"))
    )
    (net (code "97") (name "unconnected-(KEY1-Pad4)") (class "Default")
      (node (ref "KEY1") (pin "4") (pinfunction "4_4") (pintype "passive"))
    )
    (net (code "98") (name "unconnected-(U3-Pad10)") (class "Default")
      (node (ref "U3") (pin "10") (pintype "passive"))
    )
    (net (code "99") (name "unconnected-(U3-Pad11)") (class "Default")
      (node (ref "U3") (pin "11") (pintype "passive"))
    )
    (net (code "100") (name "unconnected-(U3-Pad12)") (class "Default")
      (node (ref "U3") (pin "12") (pintype "passive"))
    )
    (net (code "101") (name "unconnected-(U3-Pad13)") (class "Default")
      (node (ref "U3") (pin "13") (pintype "passive"))
    )
    (net (code "102") (name "unconnected-(U10-1A-Pad2)") (class "Default")
      (node (ref "U10") (pin "2") (pinfunction "1A_2") (pintype "passive"))
    )
    (net (code "103") (name "unconnected-(U10-1B-Pad3)") (class "Default")
      (node (ref "U10") (pin "3") (pinfunction "1B_3") (pintype "passive"))
    )
    (net (code "104") (name "unconnected-(U10-1Y-Pad4)") (class "Default")
      (node (ref "U10") (pin "4") (pinfunction "1Y_4") (pintype "passive"))
    )
    (net (code "105") (name "unconnected-(U10-2A-Pad5)") (class "Default")
      (node (ref "U10") (pin "5") (pinfunction "2A_5") (pintype "passive"))
    )
    (net (code "106") (name "unconnected-(U10-2B-Pad6)") (class "Default")
      (node (ref "U10") (pin "6") (pinfunction "2B_6") (pintype "passive"))
    )
    (net (code "107") (name "unconnected-(U10-2Y-Pad7)") (class "Default")
      (node (ref "U10") (pin "7") (pinfunction "2Y_7") (pintype "passive"))
    )
    (net (code "108") (name "unconnected-(U10-3A-Pad11)") (class "Default")
      (node (ref "U10") (pin "11") (pinfunction "3A_11") (pintype "passive"))
    )
    (net (code "109") (name "unconnected-(U10-3B-Pad10)") (class "Default")
      (node (ref "U10") (pin "10") (pinfunction "3B_10") (pintype "passive"))
    )
    (net (code "110") (name "unconnected-(U10-3Y-Pad9)") (class "Default")
      (node (ref "U10") (pin "9") (pinfunction "3Y_9") (pintype "passive"))
    )
    (net (code "111") (name "unconnected-(U12-CONTROLVOLTAGE-Pad5)") (class "Default")
      (node (ref "U12") (pin "5") (pinfunction "CONTROLVOLTAGE_5") (pintype "passive"))
    )
    (net (code "112") (name "unconnected-(U12-DISCHARGE-Pad7)") (class "Default")
      (node (ref "U12") (pin "7") (pinfunction "DISCHARGE_7") (pintype "passive"))
    )
    (net (code "113") (name "unconnected-(U12-THRESHOLD-Pad6)") (class "Default")
      (node (ref "U12") (pin "6") (pinfunction "THRESHOLD_6") (pintype "passive"))
    )
    (net (code "114") (name "unconnected-(UC4-Pad10)") (class "Default")
      (node (ref "UC4") (pin "10") (pintype "passive"))
    )
    (net (code "115") (name "unconnected-(UC4-Pad11)") (class "Default")
      (node (ref "UC4") (pin "11") (pintype "passive"))
    )
    (net (code "116") (name "unconnected-(UC4-Pad12)") (class "Default")
      (node (ref "UC4") (pin "12") (pintype "passive"))
    )
    (net (code "117") (name "unconnected-(UC4-Pad13)") (class "Default")
      (node (ref "UC4") (pin "13") (pintype "passive"))
    )
  )
)
